# power_supply.net
KiCad netlist of a schematic drawn in Altium Designer
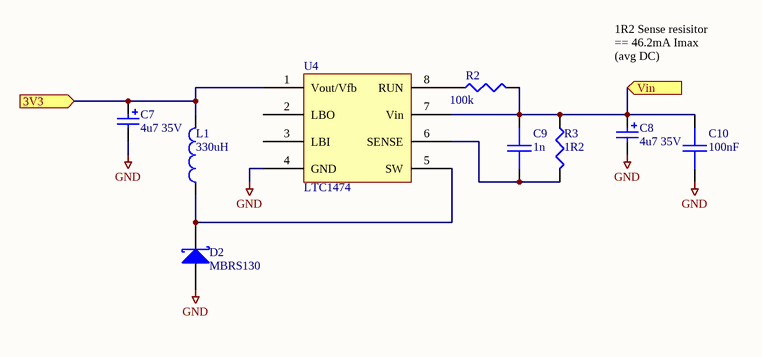
[diagram p0: power_supply.SchDoc]

(export (version "E")
  (design (tool "Eeschema 10.0.6"))
  (components
    (comp (ref "C7")
      (value "4u7 35V")
      (footprint "MCCT-CASEC")
      (description "Polarized Capacitor (Surface Mount)")
      (libsource (lib "Miscellaneous Devices") (part "Cap Pol3"))
    )
    (comp (ref "C8")
      (value "4u7 35V")
      (footprint "MCCT-CASEC")
      (description "Polarized Capacitor (Surface Mount)")
      (libsource (lib "Miscellaneous Devices") (part "Cap Pol3"))
    )
    (comp (ref "C9")
      (value "1n")
      (footprint "0603")
      (description "Capacitor")
      (libsource (lib "Miscellaneous Devices") (part "CAP"))
    )
    (comp (ref "C10")
      (value "100nF")
      (footprint "0603")
      (description "Capacitor")
      (libsource (lib "Miscellaneous Devices") (part "CAP"))
    )
    (comp (ref "D2")
      (value "MBRS130")
      (footprint "SMB")
      (description "Schottky Diode")
      (libsource (lib "RCLDQ") (part "D SCHOTTKY"))
    )
    (comp (ref "L1")
      (value "330uH")
      (footprint "1812")
      (description "Inductor")
      (libsource (lib "Miscellaneous Devices") (part "Inductor"))
    )
    (comp (ref "R2")
      (value "100k")
      (footprint "0603")
      (description "Resistor")
      (libsource (lib "RCLDQ") (part "RES1"))
    )
    (comp (ref "R3")
      (value "1R2")
      (footprint "0603")
      (description "Resistor")
      (libsource (lib "Miscellaneous Devices") (part "RES1"))
    )
    (comp (ref "U4")
      (value "LTC1474")
      (footprint "SO8")
      (description "Step-down converter")
      (libsource (lib "MiscellaneousIC") (part "LTC1474"))
    )
  )
  (nets
    (net (code "1") (name "/3V3") (class "Default")
      (node (ref "C7") (pin "1") (pinfunction "1_1") (pintype "passive"))
      (node (ref "L1") (pin "2") (pinfunction "2_2") (pintype "passive"))
      (node (ref "U4") (pin "1") (pinfunction "Vout/Vfb_1") (pintype "passive"))
    )
    (net (code "2") (name "/Vin") (class "Default")
      (node (ref "C10") (pin "1") (pinfunction "1_1") (pintype "passive"))
      (node (ref "C8") (pin "1") (pinfunction "1_1") (pintype "passive"))
      (node (ref "C9") (pin "1") (pinfunction "1_1") (pintype "passive"))
      (node (ref "R2") (pin "2") (pinfunction "2_2") (pintype "passive"))
      (node (ref "R3") (pin "1") (pinfunction "1_1") (pintype "passive"))
      (node (ref "U4") (pin "7") (pinfunction "Vin_7") (pintype "passive"))
    )
    (net (code "3") (name "GND") (class "Default")
      (node (ref "C10") (pin "2") (pinfunction "2_2") (pintype "passive"))
      (node (ref "C7") (pin "2") (pinfunction "2_2") (pintype "passive"))
      (node (ref "C8") (pin "2") (pinfunction "2_2") (pintype "passive"))
      (node (ref "D2") (pin "A") (pinfunction "A_A") (pintype "passive"))
      (node (ref "U4") (pin "4") (pinfunction "GND_4") (pintype "passive"))
    )
    (net (code "4") (name "Net-(U4-RUN)") (class "Default")
      (node (ref "R2") (pin "1") (pinfunction "1_1") (pintype "passive"))
      (node (ref "U4") (pin "8") (pinfunction "RUN_8") (pintype "passive"))
    )
    (net (code "5") (name "Net-(U4-SENSE)") (class "Default")
      (node (ref "C9") (pin "2") (pinfunction "2_2") (pintype "passive"))
      (node (ref "R3") (pin "2") (pinfunction "2_2") (pintype "passive"))
      (node (ref "U4") (pin "6") (pinfunction "SENSE_6") (pintype "passive"))
    )
    (net (code "6") (name "Net-(U4-SW)") (class "Default")
      (node (ref "D2") (pin "K") (pinfunction "K_K") (pintype "passive"))
      (node (ref "L1") (pin "1") (pinfunction "1_1") (pintype "passive"))
      (node (ref "U4") (pin "5") (pinfunction "SW_5") (pintype "passive"))
    )
    (net (code "7") (name "unconnected-(U4-LBI-Pad3)") (class "Default")
      (node (ref "U4") (pin "3") (pinfunction "LBI_3") (pintype "passive"))
    )
    (net (code "8") (name "unconnected-(U4-LBO-Pad2)") (class "Default")
      (node (ref "U4") (pin "2") (pinfunction "LBO_2") (pintype "passive"))
    )
  )
)
